# PY32F403C1xT_LINK.net
KiCad netlist of a schematic drawn in Altium Designer
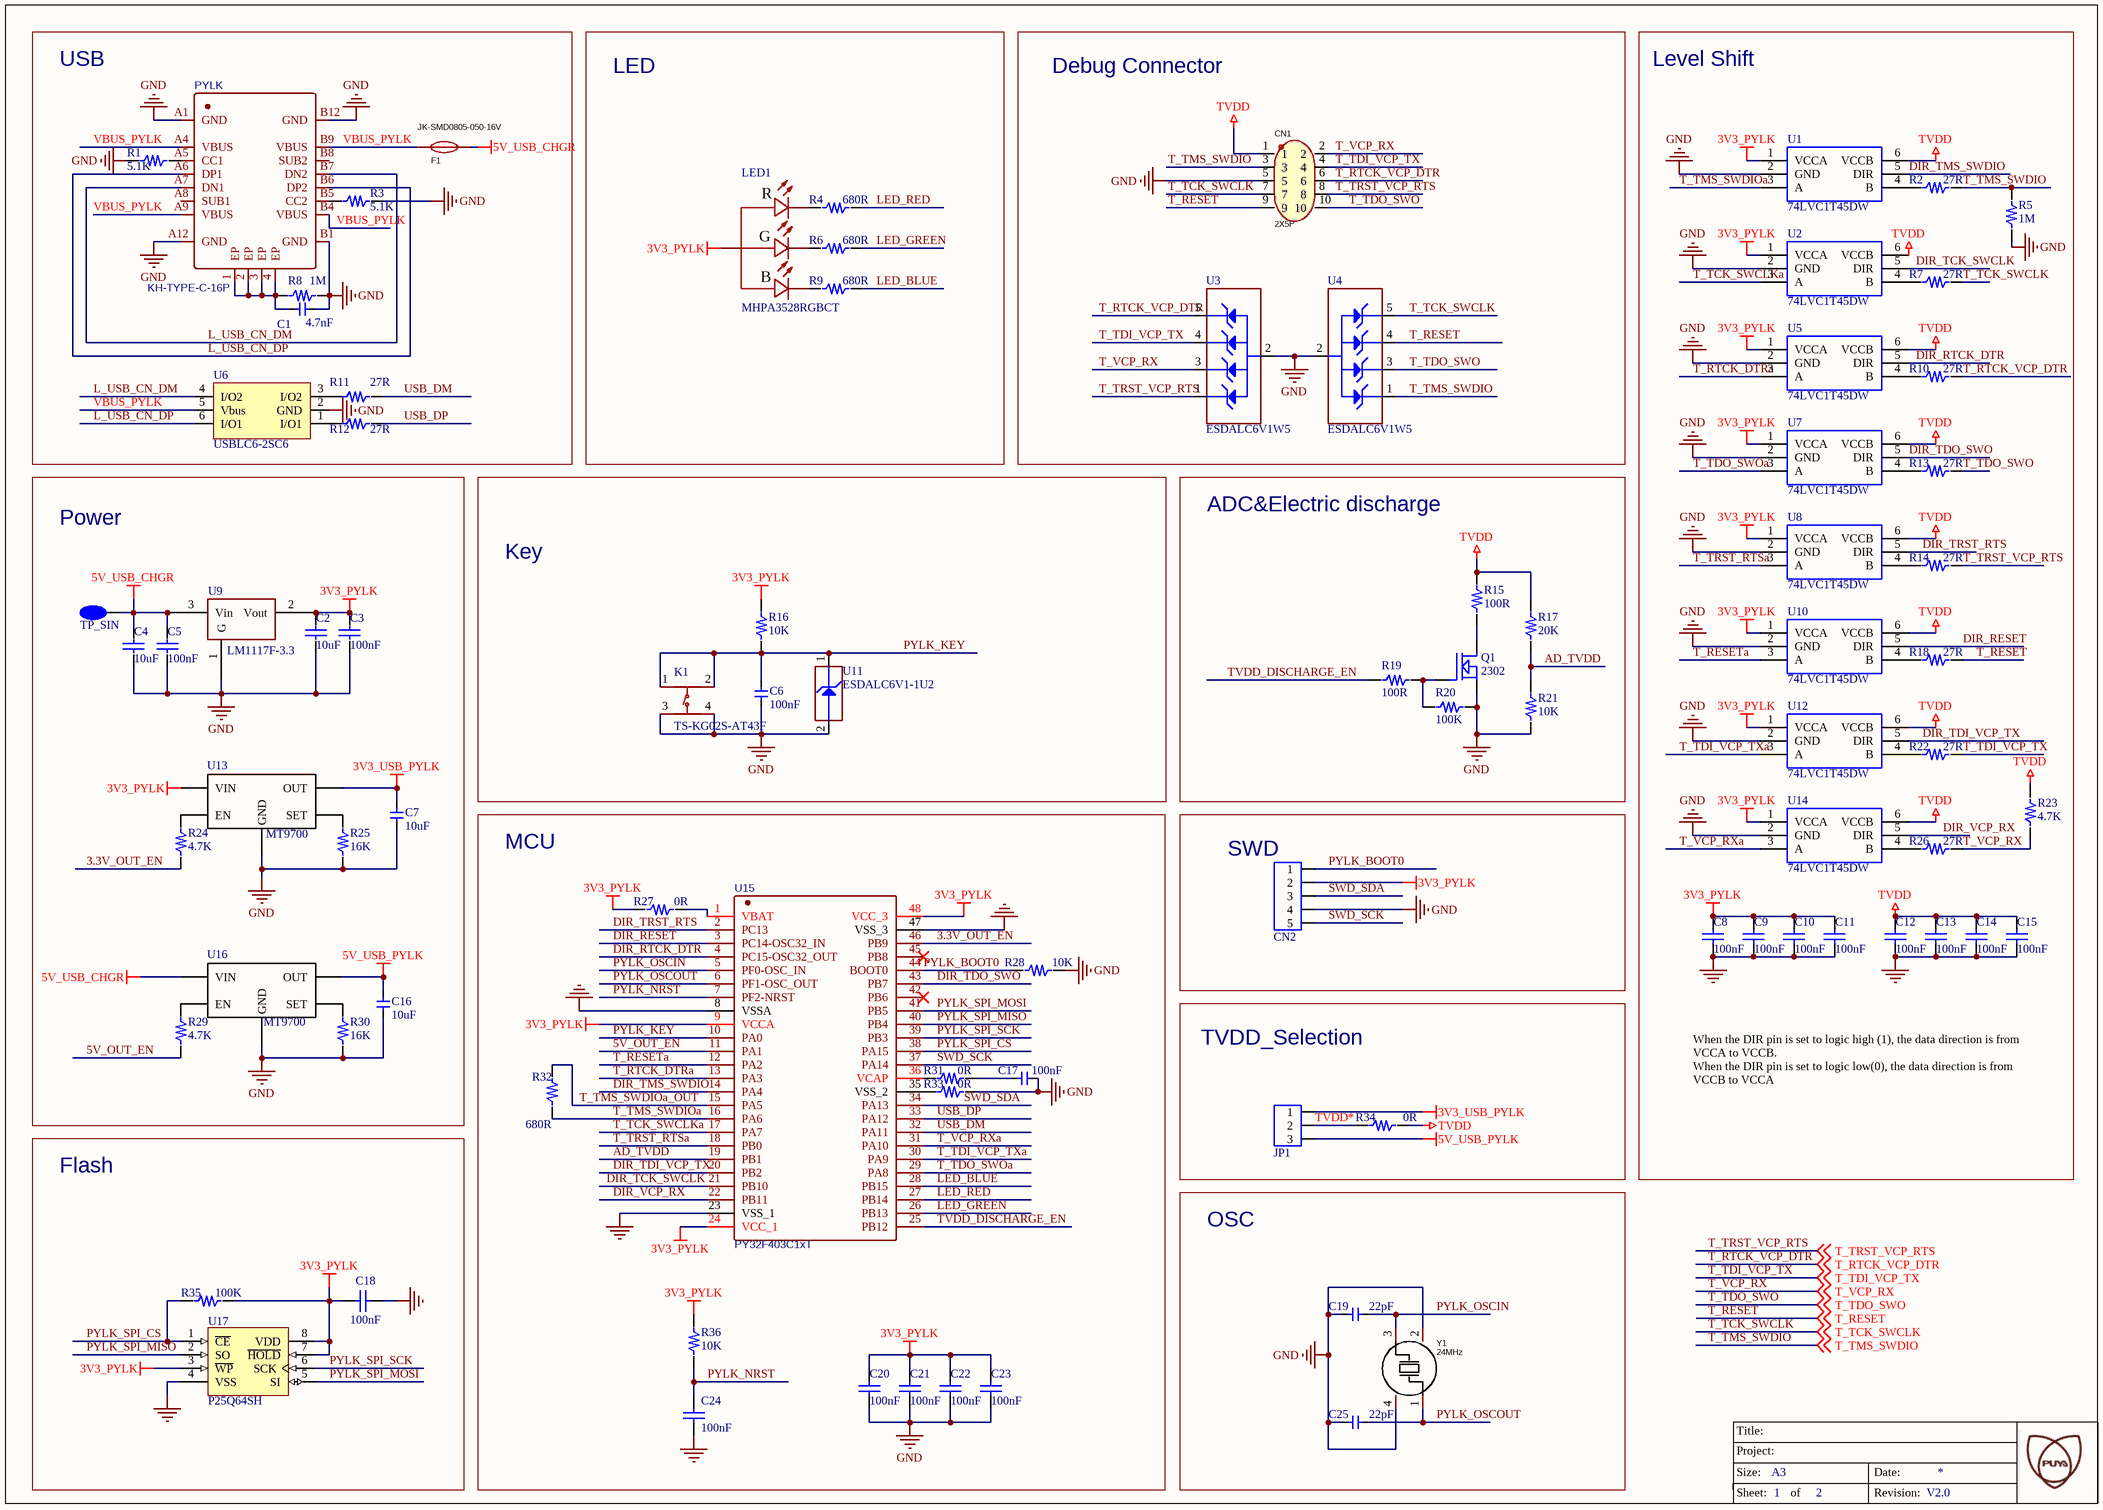
[diagram p0: PY32F403C1xT_LINK.SchDoc]

(export (version "E")
  (design (tool "Eeschema 10.0.6"))
  (components
    (comp (ref "1")
      (value "TP_SIN")
      (footprint "TP_SIN")
      (libsource (lib "PY32F403V1xT_START") (part "TP_SIN"))
    )
    (comp (ref "C1") (value "4.7nF") (footprint "C0603") (libsource (lib "ZqfAdLibrary") (part "C0603")))
    (comp (ref "C2") (value "10uF") (footprint "C0805") (libsource (lib "") (part "C0805_1")))
    (comp (ref "C3") (value "100nF") (footprint "C0603") (libsource (lib "") (part "C0603_1")))
    (comp (ref "C4") (value "10uF") (footprint "C0805") (libsource (lib "") (part "C0805_1")))
    (comp (ref "C5") (value "100nF") (footprint "C0603") (libsource (lib "") (part "C0603_1")))
    (comp (ref "C6") (value "100nF") (footprint "C0603") (libsource (lib "ZqfAdLibrary") (part "C0603")))
    (comp (ref "C7") (value "10uF") (footprint "C0805") (libsource (lib "ZqfAdLibrary") (part "C0805")))
    (comp (ref "C8")
      (value "100nF")
      (footprint "C0603")
      (description "Capacitor (Semiconductor SIM Model)")
      (libsource (lib "PRO") (part "贴片高压陶瓷电容"))
    )
    (comp (ref "C9")
      (value "100nF")
      (footprint "C0603")
      (description "Capacitor (Semiconductor SIM Model)")
      (libsource (lib "PRO") (part "贴片高压陶瓷电容"))
    )
    (comp (ref "C10")
      (value "100nF")
      (footprint "C0603")
      (description "Capacitor (Semiconductor SIM Model)")
      (libsource (lib "PRO") (part "贴片高压陶瓷电容"))
    )
    (comp (ref "C11")
      (value "100nF")
      (footprint "C0603")
      (description "Capacitor (Semiconductor SIM Model)")
      (libsource (lib "PRO") (part "贴片高压陶瓷电容"))
    )
    (comp (ref "C12")
      (value "100nF")
      (footprint "C0603")
      (description "Capacitor (Semiconductor SIM Model)")
      (libsource (lib "PRO") (part "贴片高压陶瓷电容"))
    )
    (comp (ref "C13")
      (value "100nF")
      (footprint "C0603")
      (description "Capacitor (Semiconductor SIM Model)")
      (libsource (lib "PRO") (part "贴片高压陶瓷电容"))
    )
    (comp (ref "C14")
      (value "100nF")
      (footprint "C0603")
      (description "Capacitor (Semiconductor SIM Model)")
      (libsource (lib "PRO") (part "贴片高压陶瓷电容"))
    )
    (comp (ref "C15")
      (value "100nF")
      (footprint "C0603")
      (description "Capacitor (Semiconductor SIM Model)")
      (libsource (lib "PRO") (part "贴片高压陶瓷电容"))
    )
    (comp (ref "C16") (value "10uF") (footprint "C0805") (libsource (lib "ZqfAdLibrary") (part "C0805")))
    (comp (ref "C17") (value "100nF") (footprint "C0603") (libsource (lib "ZqfAdLibrary") (part "C0603")))
    (comp (ref "C18")
      (value "100nF")
      (footprint "C0603")
      (description "Capacitor (Semiconductor SIM Model)")
      (libsource (lib "PRO") (part "贴片高压陶瓷电容"))
    )
    (comp (ref "C19") (value "22pF") (footprint "C0603") (libsource (lib "ZqfAdLibrary") (part "C0603")))
    (comp (ref "C20")
      (value "100nF")
      (footprint "C0603")
      (description "Capacitor (Semiconductor SIM Model)")
      (libsource (lib "Pro") (part "贴片高压陶瓷电容"))
    )
    (comp (ref "C21")
      (value "100nF")
      (footprint "C0603")
      (description "Capacitor (Semiconductor SIM Model)")
      (libsource (lib "PRO") (part "贴片高压陶瓷电容"))
    )
    (comp (ref "C22")
      (value "100nF")
      (footprint "C0603")
      (description "Capacitor (Semiconductor SIM Model)")
      (libsource (lib "PRO") (part "贴片高压陶瓷电容"))
    )
    (comp (ref "C23")
      (value "100nF")
      (footprint "C0603")
      (description "Capacitor (Semiconductor SIM Model)")
      (libsource (lib "PRO") (part "贴片高压陶瓷电容"))
    )
    (comp (ref "C24")
      (value "100nF")
      (footprint "C0603")
      (description "Capacitor (Semiconductor SIM Model)")
      (libsource (lib "PRO") (part "贴片高压陶瓷电容"))
    )
    (comp (ref "C25") (value "22pF") (footprint "C0603") (libsource (lib "ZqfAdLibrary") (part "C0603")))
    (comp (ref "CN1")
      (value "2X5P")
      (footprint "HDR2X5")
      (fields (field (name "MANUFACTURER") "XFCN(兴飞)") (field (name "MANUFACTURER PART") "PZ254V-12-10P"))
      (libsource (lib "PY32F403x_64pin_PYLink_STK_V1.0") (part "2X5P"))
    )
    (comp (ref "CN2") (value "CON5") (footprint "CON5") (libsource (lib "ZqfAdLibrary") (part "CON5")))
    (comp (ref "F1")
      (value "JK-SMD0805-050-16V")
      (footprint "F0805")
      (fields (field (name "MANUFACTURER") "JK(金科)"))
      (libsource (lib "altium-import") (part "root_0_JK-SMD0805-050-16V_"))
    )
    (comp (ref "JP1") (value "CON3") (footprint "CON3") (libsource (lib "ZqfAdLibrary") (part "CON3")))
    (comp (ref "K1")
      (value "TS-KG02S-AT43F")
      (footprint "SW-SMD_4P-L6.0-W6.0-P4.50-LS8.5")
      (fields (field (name "MANUFACTURER") "HANBO(汉博)"))
      (libsource (lib "altium-import") (part "root_0_TS-KG02S-AT43F_"))
    )
    (comp (ref "LED1")
      (value "MHPA3528RGBCT")
      (footprint "LED-ARRAY-SMD_4P-L3.5-W2.8-TL")
      (fields (field (name "MANUFACTURER") "MEIHUA(美华)"))
      (libsource (lib "altium-import") (part "root_0_MHPA3528RGBCT_"))
    )
    (comp (ref "PYLK")
      (value "KH-TYPE-C-16P")
      (footprint "USB-C-SMD_KH-TYPE-C-16P")
      (fields (field (name "BOM_SUPPLIER PART") "C709357") (field (name "CONTRIBUTOR") "LCSC"))
      (libsource (lib "PY32F030_StartKit_V1.4") (part "KH-TYPE-C-16P"))
    )
    (comp (ref "Q1")
      (value "2302")
      (footprint "SOT23")
      (description "MOSFET N")
      (libsource (lib "PRO") (part "MOSFET N"))
    )
    (comp (ref "R1") (value "5.1K") (footprint "R0603") (libsource (lib "ZqfAdLibrary") (part "R0603")))
    (comp (ref "R2") (value "27R") (footprint "R0603") (libsource (lib "ZqfAdLibrary") (part "R0603")))
    (comp (ref "R3") (value "5.1K") (footprint "R0603") (libsource (lib "ZqfAdLibrary") (part "R0603")))
    (comp (ref "R4") (value "680R") (footprint "R0603") (libsource (lib "ZqfAdLibrary") (part "R0603")))
    (comp (ref "R5") (value "1M") (footprint "R0603") (libsource (lib "ZqfAdLibrary") (part "R0603")))
    (comp (ref "R6") (value "680R") (footprint "R0603") (libsource (lib "ZqfAdLibrary") (part "R0603")))
    (comp (ref "R7") (value "27R") (footprint "R0603") (libsource (lib "ZqfAdLibrary") (part "R0603")))
    (comp (ref "R8") (value "1M") (footprint "R0603") (libsource (lib "ZqfAdLibrary") (part "R0603")))
    (comp (ref "R9") (value "680R") (footprint "R0603") (libsource (lib "ZqfAdLibrary") (part "R0603")))
    (comp (ref "R10") (value "27R") (footprint "R0603") (libsource (lib "ZqfAdLibrary") (part "R0603")))
    (comp (ref "R11") (value "27R") (footprint "R0603") (libsource (lib "ZqfAdLibrary") (part "R0603")))
    (comp (ref "R12") (value "27R") (footprint "R0603") (libsource (lib "ZqfAdLibrary") (part "R0603")))
    (comp (ref "R13") (value "27R") (footprint "R0603") (libsource (lib "ZqfAdLibrary") (part "R0603")))
    (comp (ref "R14") (value "27R") (footprint "R0603") (libsource (lib "ZqfAdLibrary") (part "R0603")))
    (comp (ref "R15") (value "100R") (footprint "R0805") (libsource (lib "ZqfAdLibrary") (part "R0805")))
    (comp (ref "R16") (value "10K") (footprint "R0603") (libsource (lib "ZqfAdLibrary") (part "R0603")))
    (comp (ref "R17") (value "20K") (footprint "R0603") (libsource (lib "ZqfAdLibrary") (part "R0603")))
    (comp (ref "R18") (value "27R") (footprint "R0603") (libsource (lib "ZqfAdLibrary") (part "R0603")))
    (comp (ref "R19") (value "100R") (footprint "R0603") (libsource (lib "ZqfAdLibrary") (part "R0603")))
    (comp (ref "R20") (value "100K") (footprint "R0603") (libsource (lib "ZqfAdLibrary") (part "R0603")))
    (comp (ref "R21") (value "10K") (footprint "R0603") (libsource (lib "ZqfAdLibrary") (part "R0603")))
    (comp (ref "R22") (value "27R") (footprint "R0603") (libsource (lib "ZqfAdLibrary") (part "R0603")))
    (comp (ref "R23") (value "4.7K") (footprint "R0603") (libsource (lib "ZqfAdLibrary") (part "R0603")))
    (comp (ref "R24") (value "4.7K") (footprint "R0603") (libsource (lib "ZqfAdLibrary") (part "R0603")))
    (comp (ref "R25")
      (value "16K")
      (footprint "R0603")
      (description "0603WAF1602T5E 16KΩ(1602) ±1%")
      (libsource (lib "PY32F403V1xT_START") (part "R0603_7"))
    )
    (comp (ref "R26") (value "27R") (footprint "R0603") (libsource (lib "ZqfAdLibrary") (part "R0603")))
    (comp (ref "R27") (value "0R") (footprint "JP2_SMD") (libsource (lib "ZqfAdLibrary") (part "R0603")))
    (comp (ref "R28") (value "10K") (footprint "R0603") (libsource (lib "ZqfAdLibrary") (part "R0603")))
    (comp (ref "R29") (value "4.7K") (footprint "R0603") (libsource (lib "ZqfAdLibrary") (part "R0603")))
    (comp (ref "R30")
      (value "16K")
      (footprint "R0603")
      (description "0603WAF1602T5E 16KΩ(1602) ±1%")
      (libsource (lib "PY32F403V1xT_START") (part "R0603_7"))
    )
    (comp (ref "R31") (value "0R") (footprint "JP2_SMD") (libsource (lib "ZqfAdLibrary") (part "R0603")))
    (comp (ref "R32") (value "680R") (footprint "R0603") (libsource (lib "ZqfAdLibrary") (part "R0603")))
    (comp (ref "R33") (value "0R") (footprint "JP2_SMD") (libsource (lib "ZqfAdLibrary") (part "R0603")))
    (comp (ref "R34") (value "0R") (footprint "JP2_SMD") (libsource (lib "ZqfAdLibrary") (part "R0603")))
    (comp (ref "R35") (value "100K") (footprint "R0603") (libsource (lib "ZqfAdLibrary") (part "R0603")))
    (comp (ref "R36") (value "10K") (footprint "R0603") (libsource (lib "ZqfAdLibrary") (part "R0603")))
    (comp (ref "U1") (value "74LVC1T45DW") (footprint "SOT363") (libsource (lib "集成元件") (part "74LVC1T45DW")))
    (comp (ref "U2") (value "74LVC1T45DW") (footprint "SOT363") (libsource (lib "集成元件") (part "74LVC1T45DW")))
    (comp (ref "U3")
      (value "ESDALC6V1W5")
      (footprint "ESD_SOT323-5L")
      (description "Dual Transil array for ESD protection")
      (fields
        (field (name "INTERNAL_PART_NUMBER") "MCD-00136")
        (field (name "MANUFACTURER") "STMICROELECTRONICS")
        (field (name "PROVIDED_BY") "Subcon")
      )
      (libsource (lib "PYLink") (part "ESDALC6V1W5"))
    )
    (comp (ref "U4")
      (value "ESDALC6V1W5")
      (footprint "ESD_SOT323-5L")
      (description "Dual Transil array for ESD protection")
      (fields
        (field (name "INTERNAL_PART_NUMBER") "MCD-00136")
        (field (name "MANUFACTURER") "STMICROELECTRONICS")
        (field (name "PROVIDED_BY") "Subcon")
      )
      (libsource (lib "PYLink") (part "ESDALC6V1W5"))
    )
    (comp (ref "U5") (value "74LVC1T45DW") (footprint "SOT363") (libsource (lib "集成元件") (part "74LVC1T45DW")))
    (comp (ref "U6")
      (value "USBLC6-2SC6")
      (footprint "SOT23-6")
      (libsource (lib "Private") (part "USBLC6-2SC6"))
    )
    (comp (ref "U7") (value "74LVC1T45DW") (footprint "SOT363") (libsource (lib "集成元件") (part "74LVC1T45DW")))
    (comp (ref "U8") (value "74LVC1T45DW") (footprint "SOT363") (libsource (lib "集成元件") (part "74LVC1T45DW")))
    (comp (ref "U9")
      (value "LM1117F-3.3")
      (footprint "SOT-89-3_L4.5-W2.5-P1.50-LS4.2-BR")
      (libsource (lib "PY32F403V1xT_START") (part "LM1117F-3.3"))
    )
    (comp (ref "U10")
      (value "74LVC1T45DW")
      (footprint "SOT363")
      (libsource (lib "集成元件") (part "74LVC1T45DW"))
    )
    (comp (ref "U11")
      (value "ESDALC6V1-1U2")
      (footprint "ESD_ST0201")
      (description "ESD protection 6V1")
      (fields
        (field (name "INTERNAL_PART_NUMBER") "MCD-00170")
        (field (name "MANUFACTURER") "STMICROELECTRONICS")
        (field (name "PROVIDED_BY") "Subcon")
      )
      (libsource (lib "PY32F403V1xT_START") (part "ESDALC6V1-1U2"))
    )
    (comp (ref "U12")
      (value "74LVC1T45DW")
      (footprint "SOT363")
      (libsource (lib "集成元件") (part "74LVC1T45DW"))
    )
    (comp (ref "U13")
      (value "MT9700")
      (footprint "SOT23-5")
      (libsource (lib "altium-import") (part "root_0_MT9700_"))
    )
    (comp (ref "U14")
      (value "74LVC1T45DW")
      (footprint "SOT363")
      (libsource (lib "集成元件") (part "74LVC1T45DW"))
    )
    (comp (ref "U15")
      (value "PY32F403C1xT")
      (footprint "LQFP-48_L7.0-W7.0-P0.50-LS9.0-BL")
      (description "LQFP48")
      (libsource (lib "Puya-MCU_V1.1") (part "PY32F403C1xT"))
    )
    (comp (ref "U16")
      (value "MT9700")
      (footprint "SOT23-5")
      (libsource (lib "altium-import") (part "root_0_MT9700_"))
    )
    (comp (ref "U17")
      (value "P25Q64SH")
      (footprint "SOP-8P")
      (description "SST25VF010")
      (libsource (lib "PM3.00_Pro") (part "SST25VF010"))
    )
    (comp (ref "Y1")
      (value "24MHz")
      (footprint "CRYSTAL-SMD_4P-L3.2-W2.5-BL")
      (description "±20ppm , 12.5pF , T_use: -40°C~125°C")
      (fields
        (field (name "MANUFACTURER") "ABRACON")
        (field (name "MANUFACTURER PART") "ABM8AIG-24.000MHZ-82Z-T")
      )
      (libsource (lib "ABM8AIG-24.000MHZ-82Z-T1_ABM8AIG-24.000MHZ-82Z-T") (part "ABM8AIG-24.000MHZ-82Z-T"))
    )
  )
  (nets
    (net (code "1") (name "/3.3V_OUT_EN") (class "Default")
      (node (ref "R24") (pin "1") (pinfunction "1_1") (pintype "passive"))
      (node (ref "U15") (pin "46") (pinfunction "PB9_46") (pintype "passive"))
    )
    (net (code "2") (name "/5V_OUT_EN") (class "Default")
      (node (ref "R29") (pin "1") (pinfunction "1_1") (pintype "passive"))
      (node (ref "U15") (pin "11") (pinfunction "PA1_11") (pintype "passive"))
    )
    (net (code "3") (name "/AD_TVDD") (class "Default")
      (node (ref "R17") (pin "1") (pinfunction "1_1") (pintype "passive"))
      (node (ref "R21") (pin "2") (pinfunction "2_2") (pintype "passive"))
      (node (ref "U15") (pin "19") (pinfunction "PB1_19") (pintype "passive"))
    )
    (net (code "4") (name "/DIR_RESET") (class "Default")
      (node (ref "U10") (pin "5") (pinfunction "DIR_5") (pintype "passive"))
      (node (ref "U15") (pin "3") (pinfunction "PC14-OSC32_IN_3") (pintype "passive"))
    )
    (net (code "5") (name "/DIR_RTCK_DTR") (class "Default")
      (node (ref "U15") (pin "4") (pinfunction "PC15-OSC32_OUT_4") (pintype "passive"))
      (node (ref "U5") (pin "5") (pinfunction "DIR_5") (pintype "passive"))
    )
    (net (code "6") (name "/DIR_TCK_SWCLK") (class "Default")
      (node (ref "U15") (pin "21") (pinfunction "PB10_21") (pintype "passive"))
      (node (ref "U2") (pin "5") (pinfunction "DIR_5") (pintype "passive"))
    )
    (net (code "7") (name "/DIR_TDI_VCP_TX") (class "Default")
      (node (ref "U12") (pin "5") (pinfunction "DIR_5") (pintype "passive"))
      (node (ref "U15") (pin "20") (pinfunction "PB2_20") (pintype "passive"))
    )
    (net (code "8") (name "/DIR_TDO_SWO") (class "Default")
      (node (ref "U15") (pin "43") (pinfunction "PB7_43") (pintype "passive"))
      (node (ref "U7") (pin "5") (pinfunction "DIR_5") (pintype "passive"))
    )
    (net (code "9") (name "/DIR_TMS_SWDIO") (class "Default")
      (node (ref "U1") (pin "5") (pinfunction "DIR_5") (pintype "passive"))
      (node (ref "U15") (pin "14") (pinfunction "PA4_14") (pintype "passive"))
    )
    (net (code "10") (name "/DIR_TRST_RTS") (class "Default")
      (node (ref "U15") (pin "2") (pinfunction "PC13_2") (pintype "passive"))
      (node (ref "U8") (pin "5") (pinfunction "DIR_5") (pintype "passive"))
    )
    (net (code "11") (name "/DIR_VCP_RX") (class "Default")
      (node (ref "U14") (pin "5") (pinfunction "DIR_5") (pintype "passive"))
      (node (ref "U15") (pin "22") (pinfunction "PB11_22") (pintype "passive"))
    )
    (net (code "12") (name "/LED_BLUE") (class "Default")
      (node (ref "R9") (pin "2") (pinfunction "2_2") (pintype "passive"))
      (node (ref "U15") (pin "28") (pinfunction "PB15_28") (pintype "passive"))
    )
    (net (code "13") (name "/LED_GREEN") (class "Default")
      (node (ref "R6") (pin "2") (pinfunction "2_2") (pintype "passive"))
      (node (ref "U15") (pin "26") (pinfunction "PB13_26") (pintype "passive"))
    )
    (net (code "14") (name "/LED_RED") (class "Default")
      (node (ref "R4") (pin "2") (pinfunction "2_2") (pintype "passive"))
      (node (ref "U15") (pin "27") (pinfunction "PB14_27") (pintype "passive"))
    )
    (net (code "15") (name "/L_USB_CN_DM") (class "Default")
      (node (ref "PYLK") (pin "A7") (pinfunction "DN1_A7") (pintype "passive"))
      (node (ref "PYLK") (pin "B7") (pinfunction "DN2_B7") (pintype "passive"))
      (node (ref "U6") (pin "4") (pinfunction "I/O2_4") (pintype "passive"))
    )
    (net (code "16") (name "/L_USB_CN_DP") (class "Default")
      (node (ref "PYLK") (pin "A6") (pinfunction "DP1_A6") (pintype "passive"))
      (node (ref "PYLK") (pin "B6") (pinfunction "DP2_B6") (pintype "passive"))
      (node (ref "U6") (pin "6") (pinfunction "I/O1_6") (pintype "passive"))
    )
    (net (code "17") (name "/PYLK_BOOT0") (class "Default")
      (node (ref "CN2") (pin "1") (pinfunction "1_1") (pintype "passive"))
      (node (ref "R28") (pin "1") (pinfunction "1_1") (pintype "passive"))
      (node (ref "U15") (pin "44") (pinfunction "BOOT0_44") (pintype "passive"))
    )
    (net (code "18") (name "/PYLK_KEY") (class "Default")
      (node (ref "C6") (pin "2") (pinfunction "2_2") (pintype "passive"))
      (node (ref "K1") (pin "1") (pinfunction "1_1") (pintype "passive"))
      (node (ref "K1") (pin "2") (pinfunction "2_2") (pintype "passive"))
      (node (ref "R16") (pin "1") (pinfunction "1_1") (pintype "passive"))
      (node (ref "U11") (pin "1") (pinfunction "IO1_1") (pintype "passive"))
      (node (ref "U15") (pin "10") (pinfunction "PA0_10") (pintype "passive"))
    )
    (net (code "19") (name "/PYLK_NRST") (class "Default")
      (node (ref "C24") (pin "2") (pinfunction "2_2") (pintype "passive"))
      (node (ref "R36") (pin "1") (pinfunction "1_1") (pintype "passive"))
      (node (ref "U15") (pin "7") (pinfunction "PF2-NRST_7") (pintype "passive"))
    )
    (net (code "20") (name "/PYLK_OSCIN") (class "Default")
      (node (ref "C19") (pin "2") (pinfunction "2_2") (pintype "passive"))
      (node (ref "U15") (pin "5") (pinfunction "PF0-OSC_IN_5") (pintype "passive"))
      (node (ref "Y1") (pin "3") (pinfunction "OSC2_3") (pintype "passive"))
    )
    (net (code "21") (name "/PYLK_OSCOUT") (class "Default")
      (node (ref "C25") (pin "2") (pinfunction "2_2") (pintype "passive"))
      (node (ref "U15") (pin "6") (pinfunction "PF1-OSC_OUT_6") (pintype "passive"))
      (node (ref "Y1") (pin "1") (pinfunction "OSC1_1") (pintype "passive"))
    )
    (net (code "22") (name "/PYLK_SPI_CS") (class "Default")
      (node (ref "R35") (pin "1") (pinfunction "1_1") (pintype "passive"))
      (node (ref "U15") (pin "38") (pinfunction "PA15_38") (pintype "passive"))
      (node (ref "U17") (pin "1") (pinfunction "~{CE}_1") (pintype "input"))
    )
    (net (code "23") (name "/PYLK_SPI_MISO") (class "Default")
      (node (ref "U15") (pin "40") (pinfunction "PB4_40") (pintype "passive"))
      (node (ref "U17") (pin "2") (pinfunction "SO_2") (pintype "input"))
    )
    (net (code "24") (name "/PYLK_SPI_MOSI") (class "Default")
      (node (ref "U15") (pin "41") (pinfunction "PB5_41") (pintype "passive"))
      (node (ref "U17") (pin "5") (pinfunction "SI_5") (pintype "bidirectional"))
    )
    (net (code "25") (name "/PYLK_SPI_SCK") (class "Default")
      (node (ref "U15") (pin "39") (pinfunction "PB3_39") (pintype "passive"))
      (node (ref "U17") (pin "6") (pinfunction "SCK_6") (pintype "input"))
    )
    (net (code "26") (name "/SWD_SCK") (class "Default")
      (node (ref "CN2") (pin "5") (pinfunction "5_5") (pintype "passive"))
      (node (ref "U15") (pin "37") (pinfunction "PA14_37") (pintype "passive"))
    )
    (net (code "27") (name "/SWD_SDA") (class "Default")
      (node (ref "CN2") (pin "3") (pinfunction "3_3") (pintype "passive"))
      (node (ref "U15") (pin "34") (pinfunction "PA13_34") (pintype "passive"))
    )
    (net (code "28") (name "/TVDD*") (class "Default")
      (node (ref "JP1") (pin "2") (pinfunction "2_2") (pintype "passive"))
      (node (ref "R34") (pin "1") (pinfunction "1_1") (pintype "passive"))
    )
    (net (code "29") (name "/TVDD_DISCHARGE_EN") (class "Default")
      (node (ref "R19") (pin "2") (pinfunction "2_2") (pintype "passive"))
      (node (ref "U15") (pin "25") (pinfunction "PB12_25") (pintype "passive"))
    )
    (net (code "30") (name "/T_RESETa") (class "Default")
      (node (ref "U10") (pin "3") (pinfunction "A_3") (pintype "passive"))
      (node (ref "U15") (pin "12") (pinfunction "PA2_12") (pintype "passive"))
    )
    (net (code "31") (name "/T_RTCK_DTRa") (class "Default")
      (node (ref "U15") (pin "13") (pinfunction "PA3_13") (pintype "passive"))
      (node (ref "U5") (pin "3") (pinfunction "A_3") (pintype "passive"))
    )
    (net (code "32") (name "/T_TCK_SWCLKa") (class "Default")
      (node (ref "U15") (pin "17") (pinfunction "PA7_17") (pintype "passive"))
      (node (ref "U2") (pin "3") (pinfunction "A_3") (pintype "passive"))
    )
    (net (code "33") (name "/T_TDI_VCP_TXa") (class "Default")
      (node (ref "U12") (pin "3") (pinfunction "A_3") (pintype "passive"))
      (node (ref "U15") (pin "30") (pinfunction "PA9_30") (pintype "passive"))
    )
    (net (code "34") (name "/T_TDO_SWOa") (class "Default")
      (node (ref "U15") (pin "29") (pinfunction "PA8_29") (pintype "passive"))
      (node (ref "U7") (pin "3") (pinfunction "A_3") (pintype "passive"))
    )
    (net (code "35") (name "/T_TMS_SWDIOa") (class "Default")
      (node (ref "R32") (pin "1") (pinfunction "1_1") (pintype "passive"))
      (node (ref "U1") (pin "3") (pinfunction "A_3") (pintype "passive"))
      (node (ref "U15") (pin "16") (pinfunction "PA6_16") (pintype "passive"))
    )
    (net (code "36") (name "/T_TMS_SWDIOa_OUT") (class "Default")
      (node (ref "R32") (pin "2") (pinfunction "2_2") (pintype "passive"))
      (node (ref "U15") (pin "15") (pinfunction "PA5_15") (pintype "passive"))
    )
    (net (code "37") (name "/T_TRST_RTSa") (class "Default")
      (node (ref "U15") (pin "18") (pinfunction "PB0_18") (pintype "passive"))
      (node (ref "U8") (pin "3") (pinfunction "A_3") (pintype "passive"))
    )
    (net (code "38") (name "/T_VCP_RXa") (class "Default")
      (node (ref "U14") (pin "3") (pinfunction "A_3") (pintype "passive"))
      (node (ref "U15") (pin "31") (pinfunction "PA10_31") (pintype "passive"))
    )
    (net (code "39") (name "/USB_DM") (class "Default")
      (node (ref "R11") (pin "2") (pinfunction "2_2") (pintype "passive"))
      (node (ref "U15") (pin "32") (pinfunction "PA11_32") (pintype "passive"))
    )
    (net (code "40") (name "/USB_DP") (class "Default")
      (node (ref "R12") (pin "2") (pinfunction "2_2") (pintype "passive"))
      (node (ref "U15") (pin "33") (pinfunction "PA12_33") (pintype "passive"))
    )
    (net (code "41") (name "/VBUS_PYLK") (class "Default")
      (node (ref "F1") (pin "1") (pinfunction "1_1") (pintype "passive"))
      (node (ref "PYLK") (pin "A4") (pinfunction "VBUS_A4") (pintype "passive"))
      (node (ref "PYLK") (pin "A9") (pinfunction "VBUS_A9") (pintype "passive"))
      (node (ref "PYLK") (pin "B4") (pinfunction "VBUS_B4") (pintype "passive"))
      (node (ref "PYLK") (pin "B9") (pinfunction "VBUS_B9") (pintype "passive"))
      (node (ref "U6") (pin "5") (pinfunction "Vbus_5") (pintype "passive"))
    )
    (net (code "42") (name "3V3_PYLK") (class "Default")
      (node (ref "C10") (pin "2") (pinfunction "2_2") (pintype "passive"))
      (node (ref "C11") (pin "2") (pinfunction "2_2") (pintype "passive"))
      (node (ref "C18") (pin "2") (pinfunction "2_2") (pintype "passive"))
      (node (ref "C2") (pin "2") (pinfunction "2_2") (pintype "passive"))
      (node (ref "C20") (pin "2") (pinfunction "2_2") (pintype "passive"))
      (node (ref "C21") (pin "2") (pinfunction "2_2") (pintype "passive"))
      (node (ref "C22") (pin "2") (pinfunction "2_2") (pintype "passive"))
      (node (ref "C23") (pin "2") (pinfunction "2_2") (pintype "passive"))
      (node (ref "C3") (pin "2") (pinfunction "2_2") (pintype "passive"))
      (node (ref "C8") (pin "2") (pinfunction "2_2") (pintype "passive"))
      (node (ref "C9") (pin "2") (pinfunction "2_2") (pintype "passive"))
      (node (ref "CN2") (pin "2") (pinfunction "2_2") (pintype "passive"))
      (node (ref "LED1") (pin "1") (pinfunction "-_1") (pintype "passive"))
      (node (ref "R16") (pin "2") (pinfunction "2_2") (pintype "passive"))
      (node (ref "R27") (pin "1") (pinfunction "1_1") (pintype "passive"))
      (node (ref "R35") (pin "2") (pinfunction "2_2") (pintype "passive"))
      (node (ref "R36") (pin "2") (pinfunction "2_2") (pintype "passive"))
      (node (ref "U1") (pin "1") (pinfunction "VCCA_1") (pintype "passive"))
      (node (ref "U10") (pin "1") (pinfunction "VCCA_1") (pintype "passive"))
      (node (ref "U12") (pin "1") (pinfunction "VCCA_1") (pintype "passive"))
      (node (ref "U13") (pin "5") (pinfunction "VIN_5") (pintype "passive"))
      (node (ref "U14") (pin "1") (pinfunction "VCCA_1") (pintype "passive"))
      (node (ref "U15") (pin "24") (pinfunction "VCC_1_24") (pintype "passive"))
      (node (ref "U15") (pin "48") (pinfunction "VCC_3_48") (pintype "passive"))
      (node (ref "U15") (pin "9") (pinfunction "VCCA_9") (pintype "passive"))
      (node (ref "U17") (pin "3") (pinfunction "~{WP}_3") (pintype "input"))
      (node (ref "U17") (pin "7") (pinfunction "~{HOLD}_7") (pintype "input"))
      (node (ref "U17") (pin "8") (pinfunction "VDD_8") (pintype "power_in"))
      (node (ref "U2") (pin "1") (pinfunction "VCCA_1") (pintype "passive"))
      (node (ref "U5") (pin "1") (pinfunction "VCCA_1") (pintype "passive"))
      (node (ref "U7") (pin "1") (pinfunction "VCCA_1") (pintype "passive"))
      (node (ref "U8") (pin "1") (pinfunction "VCCA_1") (pintype "passive"))
      (node (ref "U9") (pin "2") (pinfunction "Vout_2") (pintype "passive"))
    )
    (net (code "43") (name "3V3_USB_PYLK") (class "Default")
      (node (ref "C7") (pin "2") (pinfunction "2_2") (pintype "passive"))
      (node (ref "JP1") (pin "1") (pinfunction "1_1") (pintype "passive"))
      (node (ref "U13") (pin "1") (pinfunction "OUT_1") (pintype "passive"))
    )
    (net (code "44") (name "5V_USB_CHGR") (class "Default")
      (node (ref "1") (pin "1") (pinfunction "TP_SIN_1") (pintype "passive"))
      (node (ref "C4") (pin "2") (pinfunction "2_2") (pintype "passive"))
      (node (ref "C5") (pin "2") (pinfunction "2_2") (pintype "passive"))
      (node (ref "F1") (pin "2") (pinfunction "2_2") (pintype "passive"))
      (node (ref "U16") (pin "5") (pinfunction "VIN_5") (pintype "passive"))
      (node (ref "U9") (pin "3") (pinfunction "Vin_3") (pintype "passive"))
    )
    (net (code "45") (name "5V_USB_PYLK") (class "Default")
      (node (ref "C16") (pin "2") (pinfunction "2_2") (pintype "passive"))
      (node (ref "JP1") (pin "3") (pinfunction "3_3") (pintype "passive"))
      (node (ref "U16") (pin "1") (pinfunction "OUT_1") (pintype "passive"))
    )
    (net (code "46") (name "GND") (class "Default")
      (node (ref "C1") (pin "1") (pinfunction "1_1") (pintype "passive"))
      (node (ref "C10") (pin "1") (pinfunction "1_1") (pintype "passive"))
      (node (ref "C11") (pin "1") (pinfunction "1_1") (pintype "passive"))
      (node (ref "C12") (pin "1") (pinfunction "1_1") (pintype "passive"))
      (node (ref "C13") (pin "1") (pinfunction "1_1") (pintype "passive"))
      (node (ref "C14") (pin "1") (pinfunction "1_1") (pintype "passive"))
      (node (ref "C15") (pin "1") (pinfunction "1_1") (pintype "passive"))
      (node (ref "C16") (pin "1") (pinfunction "1_1") (pintype "passive"))
      (node (ref "C17") (pin "1") (pinfunction "1_1") (pintype "passive"))
      (node (ref "C18") (pin "1") (pinfunction "1_1") (pintype "passive"))
      (node (ref "C19") (pin "1") (pinfunction "1_1") (pintype "passive"))
      (node (ref "C2") (pin "1") (pinfunction "1_1") (pintype "passive"))
      (node (ref "C20") (pin "1") (pinfunction "1_1") (pintype "passive"))
      (node (ref "C21") (pin "1") (pinfunction "1_1") (pintype "passive"))
      (node (ref "C22") (pin "1") (pinfunction "1_1") (pintype "passive"))
      (node (ref "C23") (pin "1") (pinfunction "1_1") (pintype "passive"))
      (node (ref "C24") (pin "1") (pinfunction "1_1") (pintype "passive"))
      (node (ref "C25") (pin "1") (pinfunction "1_1") (pintype "passive"))
      (node (ref "C3") (pin "1") (pinfunction "1_1") (pintype "passive"))
      (node (ref "C4") (pin "1") (pinfunction "1_1") (pintype "passive"))
      (node (ref "C5") (pin "1") (pinfunction "1_1") (pintype "passive"))
      (node (ref "C6") (pin "1") (pinfunction "1_1") (pintype "passive"))
      (node (ref "C7") (pin "1") (pinfunction "1_1") (pintype "passive"))
      (node (ref "C8") (pin "1") (pinfunction "1_1") (pintype "passive"))
      (node (ref "C9") (pin "1") (pinfunction "1_1") (pintype "passive"))
      (node (ref "CN1") (pin "5") (pinfunction "5_5") (pintype "passive"))
      (node (ref "CN2") (pin "4") (pinfunction "4_4") (pintype "passive"))
      (node (ref "K1") (pin "3") (pinfunction "3_3") (pintype "passive"))
      (node (ref "K1") (pin "4") (pinfunction "4_4") (pintype "passive"))
      (node (ref "PYLK") (pin "A1") (pinfunction "GND_A1") (pintype "passive"))
      (node (ref "PYLK") (pin "A12") (pinfunction "GND_A12") (pintype "passive"))
      (node (ref "PYLK") (pin "B1") (pinfunction "GND_B1") (pintype "passive"))
      (node (ref "PYLK") (pin "B12") (pinfunction "GND_B12") (pintype "passive"))
      (node (ref "Q1") (pin "2") (pinfunction "S_2") (pintype "passive"))
      (node (ref "R1") (pin "1") (pinfunction "1_1") (pintype "passive"))
      (node (ref "R20") (pin "1") (pinfunction "1_1") (pintype "passive"))
      (node (ref "R21") (pin "1") (pinfunction "1_1") (pintype "passive"))
      (node (ref "R25") (pin "1") (pinfunction "1_1") (pintype "passive"))
      (node (ref "R28") (pin "2") (pinfunction "2_2") (pintype "passive"))
      (node (ref "R3") (pin "2") (pinfunction "2_2") (pintype "passive"))
      (node (ref "R30") (pin "1") (pinfunction "1_1") (pintype "passive"))
      (node (ref "R33") (pin "2") (pinfunction "2_2") (pintype "passive"))
      (node (ref "R5") (pin "1") (pinfunction "1_1") (pintype "passive"))
      (node (ref "R8") (pin "2") (pinfunction "2_2") (pintype "passive"))
      (node (ref "U1") (pin "2") (pinfunction "GND_2") (pintype "passive"))
      (node (ref "U10") (pin "2") (pinfunction "GND_2") (pintype "passive"))
      (node (ref "U11") (pin "2") (pinfunction "GND_2") (pintype "passive"))
      (node (ref "U12") (pin "2") (pinfunction "GND_2") (pintype "passive"))
      (node (ref "U13") (pin "2") (pinfunction "GND_2") (pintype "passive"))
      (node (ref "U14") (pin "2") (pinfunction "GND_2") (pintype "passive"))
      (node (ref "U15") (pin "23") (pinfunction "VSS_1_23") (pintype "passive"))
      (node (ref "U15") (pin "47") (pinfunction "VSS_3_47") (pintype "passive"))
      (node (ref "U15") (pin "8") (pinfunction "VSSA_8") (pintype "passive"))
      (node (ref "U16") (pin "2") (pinfunction "GND_2") (pintype "passive"))
      (node (ref "U17") (pin "4") (pinfunction "VSS_4") (pintype "power_in"))
      (node (ref "U2") (pin "2") (pinfunction "GND_2") (pintype "passive"))
      (node (ref "U3") (pin "2") (pinfunction "GND_2") (pintype "passive"))
      (node (ref "U4") (pin "2") (pinfunction "GND_2") (pintype "passive"))
      (node (ref "U5") (pin "2") (pinfunction "GND_2") (pintype "passive"))
      (node (ref "U6") (pin "2") (pinfunction "GND_2") (pintype "passive"))
      (node (ref "U7") (pin "2") (pinfunction "GND_2") (pintype "passive"))
      (node (ref "U8") (pin "2") (pinfunction "GND_2") (pintype "passive"))
      (node (ref "U9") (pin "1") (pinfunction "G_1") (pintype "passive"))
      (node (ref "Y1") (pin "2") (pinfunction "GND_2") (pintype "passive"))
      (node (ref "Y1") (pin "4") (pinfunction "GND_4") (pintype "passive"))
    )
    (net (code "47") (name "Net-(C1-Pad2)") (class "Default")
      (node (ref "C1") (pin "2") (pinfunction "2_2") (pintype "passive"))
      (node (ref "PYLK") (pin "1") (pinfunction "EP_1") (pintype "passive"))
      (node (ref "PYLK") (pin "2") (pinfunction "EP_2") (pintype "passive"))
      (node (ref "PYLK") (pin "3") (pinfunction "EP_3") (pintype "passive"))
      (node (ref "PYLK") (pin "4") (pinfunction "EP_4") (pintype "passive"))
      (node (ref "R8") (pin "1") (pinfunction "1_1") (pintype "passive"))
    )
    (net (code "48") (name "Net-(C17-Pad2)") (class "Default")
      (node (ref "C17") (pin "2") (pinfunction "2_2") (pintype "passive"))
      (node (ref "R31") (pin "2") (pinfunction "2_2") (pintype "passive"))
    )
    (net (code "49") (name "Net-(LED1---Pad2)") (class "Default")
      (node (ref "LED1") (pin "2") (pinfunction "-_2") (pintype "passive"))
      (node (ref "R9") (pin "1") (pinfunction "1_1") (pintype "passive"))
    )
    (net (code "50") (name "Net-(LED1---Pad3)") (class "Default")
      (node (ref "LED1") (pin "3") (pinfunction "-_3") (pintype "passive"))
      (node (ref "R6") (pin "1") (pinfunction "1_1") (pintype "passive"))
    )
    (net (code "51") (name "Net-(LED1---Pad4)") (class "Default")
      (node (ref "LED1") (pin "4") (pinfunction "-_4") (pintype "passive"))
      (node (ref "R4") (pin "1") (pinfunction "1_1") (pintype "passive"))
    )
    (net (code "52") (name "Net-(PYLK-CC1)") (class "Default")
      (node (ref "PYLK") (pin "A5") (pinfunction "CC1_A5") (pintype "passive"))
      (node (ref "R1") (pin "2") (pinfunction "2_2") (pintype "passive"))
    )
    (net (code "53") (name "Net-(PYLK-CC2)") (class "Default")
      (node (ref "PYLK") (pin "B5") (pinfunction "CC2_B5") (pintype "passive"))
      (node (ref "R3") (pin "1") (pinfunction "1_1") (pintype "passive"))
    )
    (net (code "54") (name "Net-(Q1-D)") (class "Default")
      (node (ref "Q1") (pin "3") (pinfunction "D_3") (pintype "passive"))
      (node (ref "R15") (pin "1") (pinfunction "1_1") (pintype "passive"))
    )
    (net (code "55") (name "Net-(Q1-G)") (class "Default")
      (node (ref "Q1") (pin "1") (pinfunction "G_1") (pintype "passive"))
      (node (ref "R19") (pin "1") (pinfunction "1_1") (pintype "passive"))
      (node (ref "R20") (pin "2") (pinfunction "2_2") (pintype "passive"))
    )
    (net (code "56") (name "Net-(R11-Pad1)") (class "Default")
      (node (ref "R11") (pin "1") (pinfunction "1_1") (pintype "passive"))
      (node (ref "U6") (pin "3") (pinfunction "I/O2_3") (pintype "passive"))
    )
    (net (code "57") (name "Net-(R12-Pad1)") (class "Default")
      (node (ref "R12") (pin "1") (pinfunction "1_1") (pintype "passive"))
      (node (ref "U6") (pin "1") (pinfunction "I/O1_1") (pintype "passive"))
    )
    (net (code "58") (name "Net-(U1-B)") (class "Default")
      (node (ref "R2") (pin "1") (pinfunction "1_1") (pintype "passive"))
      (node (ref "U1") (pin "4") (pinfunction "B_4") (pintype "passive"))
    )
    (net (code "59") (name "Net-(U2-B)") (class "Default")
      (node (ref "R7") (pin "1") (pinfunction "1_1") (pintype "passive"))
      (node (ref "U2") (pin "4") (pinfunction "B_4") (pintype "passive"))
    )
    (net (code "60") (name "Net-(U5-B)") (class "Default")
      (node (ref "R10") (pin "1") (pinfunction "1_1") (pintype "passive"))
      (node (ref "U5") (pin "4") (pinfunction "B_4") (pintype "passive"))
    )
    (net (code "61") (name "Net-(U7-B)") (class "Default")
      (node (ref "R13") (pin "1") (pinfunction "1_1") (pintype "passive"))
      (node (ref "U7") (pin "4") (pinfunction "B_4") (pintype "passive"))
    )
    (net (code "62") (name "Net-(U8-B)") (class "Default")
      (node (ref "R14") (pin "1") (pinfunction "1_1") (pintype "passive"))
      (node (ref "U8") (pin "4") (pinfunction "B_4") (pintype "passive"))
    )
    (net (code "63") (name "Net-(U10-B)") (class "Default")
      (node (ref "R18") (pin "1") (pinfunction "1_1") (pintype "passive"))
      (node (ref "U10") (pin "4") (pinfunction "B_4") (pintype "passive"))
    )
    (net (code "64") (name "Net-(U12-B)") (class "Default")
      (node (ref "R22") (pin "1") (pinfunction "1_1") (pintype "passive"))
      (node (ref "U12") (pin "4") (pinfunction "B_4") (pintype "passive"))
    )
    (net (code "65") (name "Net-(U13-EN)") (class "Default")
      (node (ref "R24") (pin "2") (pinfunction "2_2") (pintype "passive"))
      (node (ref "U13") (pin "4") (pinfunction "EN_4") (pintype "passive"))
    )
    (net (code "66") (name "Net-(U13-SET)") (class "Default")
      (node (ref "R25") (pin "2") (pinfunction "2_2") (pintype "passive"))
      (node (ref "U13") (pin "3") (pinfunction "SET_3") (pintype "passive"))
    )
    (net (code "67") (name "Net-(U14-B)") (class "Default")
      (node (ref "R26") (pin "1") (pinfunction "1_1") (pintype "passive"))
      (node (ref "U14") (pin "4") (pinfunction "B_4") (pintype "passive"))
    )
    (net (code "68") (name "Net-(U15-VBAT)") (class "Default")
      (node (ref "R27") (pin "2") (pinfunction "2_2") (pintype "passive"))
      (node (ref "U15") (pin "1") (pinfunction "VBAT_1") (pintype "passive"))
    )
    (net (code "69") (name "Net-(U15-VCAP)") (class "Default")
      (node (ref "R31") (pin "1") (pinfunction "1_1") (pintype "passive"))
      (node (ref "U15") (pin "36") (pinfunction "VCAP_36") (pintype "passive"))
    )
    (net (code "70") (name "Net-(U15-VSS_2)") (class "Default")
      (node (ref "R33") (pin "1") (pinfunction "1_1") (pintype "passive"))
      (node (ref "U15") (pin "35") (pinfunction "VSS_2_35") (pintype "passive"))
    )
    (net (code "71") (name "Net-(U16-EN)") (class "Default")
      (node (ref "R29") (pin "2") (pinfunction "2_2") (pintype "passive"))
      (node (ref "U16") (pin "4") (pinfunction "EN_4") (pintype "passive"))
    )
    (net (code "72") (name "Net-(U16-SET)") (class "Default")
      (node (ref "R30") (pin "2") (pinfunction "2_2") (pintype "passive"))
      (node (ref "U16") (pin "3") (pinfunction "SET_3") (pintype "passive"))
    )
    (net (code "73") (name "TVDD") (class "Default")
      (node (ref "C12") (pin "2") (pinfunction "2_2") (pintype "passive"))
      (node (ref "C13") (pin "2") (pinfunction "2_2") (pintype "passive"))
      (node (ref "C14") (pin "2") (pinfunction "2_2") (pintype "passive"))
      (node (ref "C15") (pin "2") (pinfunction "2_2") (pintype "passive"))
      (node (ref "CN1") (pin "1") (pinfunction "1_1") (pintype "passive"))
      (node (ref "R15") (pin "2") (pinfunction "2_2") (pintype "passive"))
      (node (ref "R17") (pin "2") (pinfunction "2_2") (pintype "passive"))
      (node (ref "R23") (pin "2") (pinfunction "2_2") (pintype "passive"))
      (node (ref "R34") (pin "2") (pinfunction "2_2") (pintype "passive"))
      (node (ref "U1") (pin "6") (pinfunction "VCCB_6") (pintype "passive"))
      (node (ref "U10") (pin "6") (pinfunction "VCCB_6") (pintype "passive"))
      (node (ref "U12") (pin "6") (pinfunction "VCCB_6") (pintype "passive"))
      (node (ref "U14") (pin "6") (pinfunction "VCCB_6") (pintype "passive"))
      (node (ref "U2") (pin "6") (pinfunction "VCCB_6") (pintype "passive"))
      (node (ref "U5") (pin "6") (pinfunction "VCCB_6") (pintype "passive"))
      (node (ref "U7") (pin "6") (pinfunction "VCCB_6") (pintype "passive"))
      (node (ref "U8") (pin "6") (pinfunction "VCCB_6") (pintype "passive"))
    )
    (net (code "74") (name "T_RESET") (class "Default")
      (node (ref "CN1") (pin "9") (pinfunction "9_9") (pintype "passive"))
      (node (ref "R18") (pin "2") (pinfunction "2_2") (pintype "passive"))
      (node (ref "U4") (pin "4") (pinfunction "IO3_4") (pintype "passive"))
    )
    (net (code "75") (name "T_RTCK_VCP_DTR") (class "Default")
      (node (ref "CN1") (pin "6") (pinfunction "6_6") (pintype "passive"))
      (node (ref "R10") (pin "2") (pinfunction "2_2") (pintype "passive"))
      (node (ref "U3") (pin "5") (pinfunction "IO4_5") (pintype "passive"))
    )
    (net (code "76") (name "T_TCK_SWCLK") (class "Default")
      (node (ref "CN1") (pin "7") (pinfunction "7_7") (pintype "passive"))
      (node (ref "R7") (pin "2") (pinfunction "2_2") (pintype "passive"))
      (node (ref "U4") (pin "5") (pinfunction "IO4_5") (pintype "passive"))
    )
    (net (code "77") (name "T_TDI_VCP_TX") (class "Default")
      (node (ref "CN1") (pin "4") (pinfunction "4_4") (pintype "passive"))
      (node (ref "R22") (pin "2") (pinfunction "2_2") (pintype "passive"))
      (node (ref "U3") (pin "4") (pinfunction "IO3_4") (pintype "passive"))
    )
    (net (code "78") (name "T_TDO_SWO") (class "Default")
      (node (ref "CN1") (pin "10") (pinfunction "10_10") (pintype "passive"))
      (node (ref "R13") (pin "2") (pinfunction "2_2") (pintype "passive"))
      (node (ref "U4") (pin "3") (pinfunction "IO2_3") (pintype "passive"))
    )
    (net (code "79") (name "T_TMS_SWDIO") (class "Default")
      (node (ref "CN1") (pin "3") (pinfunction "3_3") (pintype "passive"))
      (node (ref "R2") (pin "2") (pinfunction "2_2") (pintype "passive"))
      (node (ref "R5") (pin "2") (pinfunction "2_2") (pintype "passive"))
      (node (ref "U4") (pin "1") (pinfunction "IO1_1") (pintype "passive"))
    )
    (net (code "80") (name "T_TRST_VCP_RTS") (class "Default")
      (node (ref "CN1") (pin "8") (pinfunction "8_8") (pintype "passive"))
      (node (ref "R14") (pin "2") (pinfunction "2_2") (pintype "passive"))
      (node (ref "U3") (pin "1") (pinfunction "IO1_1") (pintype "passive"))
    )
    (net (code "81") (name "T_VCP_RX") (class "Default")
      (node (ref "CN1") (pin "2") (pinfunction "2_2") (pintype "passive"))
      (node (ref "R23") (pin "1") (pinfunction "1_1") (pintype "passive"))
      (node (ref "R26") (pin "2") (pinfunction "2_2") (pintype "passive"))
      (node (ref "U3") (pin "3") (pinfunction "IO2_3") (pintype "passive"))
    )
    (net (code "82") (name "unconnected-(PYLK-SUB1-PadA8)") (class "Default")
      (node (ref "PYLK") (pin "A8") (pinfunction "SUB1_A8") (pintype "passive"))
    )
    (net (code "83") (name "unconnected-(PYLK-SUB2-PadB8)") (class "Default")
      (node (ref "PYLK") (pin "B8") (pinfunction "SUB2_B8") (pintype "passive"))
    )
    (net (code "84") (name "unconnected-(U15-PB6-Pad42)") (class "Default")
      (node (ref "U15") (pin "42") (pinfunction "PB6_42") (pintype "passive+no_connect"))
    )
    (net (code "85") (name "unconnected-(U15-PB8-Pad45)") (class "Default")
      (node (ref "U15") (pin "45") (pinfunction "PB8_45") (pintype "passive+no_connect"))
    )
  )
)
